# logic_analyser.net
KiCad netlist of a schematic drawn in EAGLE
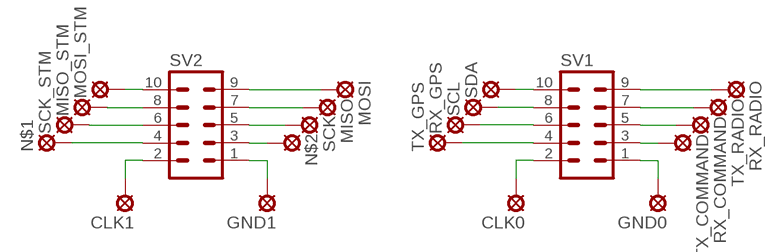
[diagram p0: schematic, sheet 1]

(export (version "E")
  (design (tool "Eeschema 10.0.6"))
  (components
    (comp (ref "CLK0")
      (value "LSP10")
      (footprint "eagle-import:LSP10")
      (libsource (lib "eagle-import") (part "LSP10"))
    )
    (comp (ref "CLK1")
      (value "LSP10")
      (footprint "eagle-import:LSP10")
      (libsource (lib "eagle-import") (part "LSP10"))
    )
    (comp (ref "GND0")
      (value "LSP10")
      (footprint "eagle-import:LSP10")
      (libsource (lib "eagle-import") (part "LSP10"))
    )
    (comp (ref "GND1")
      (value "LSP10")
      (footprint "eagle-import:LSP10")
      (libsource (lib "eagle-import") (part "LSP10"))
    )
    (comp (ref "MISO")
      (value "LSP10")
      (footprint "eagle-import:LSP10")
      (libsource (lib "eagle-import") (part "LSP10"))
    )
    (comp (ref "MISO_STM")
      (value "LSP10")
      (footprint "eagle-import:LSP10")
      (libsource (lib "eagle-import") (part "LSP10"))
    )
    (comp (ref "MOSI")
      (value "LSP10")
      (footprint "eagle-import:LSP10")
      (libsource (lib "eagle-import") (part "LSP10"))
    )
    (comp (ref "MOSI_STM")
      (value "LSP10")
      (footprint "eagle-import:LSP10")
      (libsource (lib "eagle-import") (part "LSP10"))
    )
    (comp (ref "N$1")
      (value "LSP10")
      (footprint "eagle-import:LSP10")
      (libsource (lib "eagle-import") (part "LSP10"))
    )
    (comp (ref "N$2")
      (value "LSP10")
      (footprint "eagle-import:LSP10")
      (libsource (lib "eagle-import") (part "LSP10"))
    )
    (comp (ref "RX_COMMAND")
      (value "LSP10")
      (footprint "eagle-import:LSP10")
      (libsource (lib "eagle-import") (part "LSP10"))
    )
    (comp (ref "RX_GPS")
      (value "LSP10")
      (footprint "eagle-import:LSP10")
      (libsource (lib "eagle-import") (part "LSP10"))
    )
    (comp (ref "RX_RADIO")
      (value "LSP10")
      (footprint "eagle-import:LSP10")
      (libsource (lib "eagle-import") (part "LSP10"))
    )
    (comp (ref "SCK")
      (value "LSP10")
      (footprint "eagle-import:LSP10")
      (libsource (lib "eagle-import") (part "LSP10"))
    )
    (comp (ref "SCK_STM")
      (value "LSP10")
      (footprint "eagle-import:LSP10")
      (libsource (lib "eagle-import") (part "LSP10"))
    )
    (comp (ref "SCL")
      (value "LSP10")
      (footprint "eagle-import:LSP10")
      (libsource (lib "eagle-import") (part "LSP10"))
    )
    (comp (ref "SDA")
      (value "LSP10")
      (footprint "eagle-import:LSP10")
      (libsource (lib "eagle-import") (part "LSP10"))
    )
    (comp (ref "SV1")
      (value "MA05-2")
      (footprint "eagle-import:MA05-2")
      (libsource (lib "eagle-import") (part "MA05-2"))
    )
    (comp (ref "SV2")
      (value "MA05-2")
      (footprint "eagle-import:MA05-2")
      (libsource (lib "eagle-import") (part "MA05-2"))
    )
    (comp (ref "TX_COMMAND")
      (value "LSP10")
      (footprint "eagle-import:LSP10")
      (libsource (lib "eagle-import") (part "LSP10"))
    )
    (comp (ref "TX_GPS")
      (value "LSP10")
      (footprint "eagle-import:LSP10")
      (libsource (lib "eagle-import") (part "LSP10"))
    )
    (comp (ref "TX_RADIO")
      (value "LSP10")
      (footprint "eagle-import:LSP10")
      (libsource (lib "eagle-import") (part "LSP10"))
    )
  )
  (nets
    (net (code "1") (name "Net-(CLK0-PadMP)") (class "Default")
      (node (ref "CLK0") (pin "MP") (pinfunction "MP_MP") (pintype "passive"))
      (node (ref "SV1") (pin "2") (pinfunction "2_2") (pintype "passive"))
    )
    (net (code "2") (name "Net-(CLK1-PadMP)") (class "Default")
      (node (ref "CLK1") (pin "MP") (pinfunction "MP_MP") (pintype "passive"))
      (node (ref "SV2") (pin "2") (pinfunction "2_2") (pintype "passive"))
    )
    (net (code "3") (name "Net-(GND0-PadMP)") (class "Default")
      (node (ref "GND0") (pin "MP") (pinfunction "MP_MP") (pintype "passive"))
      (node (ref "SV1") (pin "1") (pinfunction "1_1") (pintype "passive"))
    )
    (net (code "4") (name "Net-(GND1-PadMP)") (class "Default")
      (node (ref "GND1") (pin "MP") (pinfunction "MP_MP") (pintype "passive"))
      (node (ref "SV2") (pin "1") (pinfunction "1_1") (pintype "passive"))
    )
    (net (code "5") (name "Net-(MISO-PadMP)") (class "Default")
      (node (ref "MISO") (pin "MP") (pinfunction "MP_MP") (pintype "passive"))
      (node (ref "SV2") (pin "7") (pinfunction "7_7") (pintype "passive"))
    )
    (net (code "6") (name "Net-(MISO_STM-PadMP)") (class "Default")
      (node (ref "MISO_STM") (pin "MP") (pinfunction "MP_MP") (pintype "passive"))
      (node (ref "SV2") (pin "8") (pinfunction "8_8") (pintype "passive"))
    )
    (net (code "7") (name "Net-(MOSI-PadMP)") (class "Default")
      (node (ref "MOSI") (pin "MP") (pinfunction "MP_MP") (pintype "passive"))
      (node (ref "SV2") (pin "9") (pinfunction "9_9") (pintype "passive"))
    )
    (net (code "8") (name "Net-(MOSI_STM-PadMP)") (class "Default")
      (node (ref "MOSI_STM") (pin "MP") (pinfunction "MP_MP") (pintype "passive"))
      (node (ref "SV2") (pin "10") (pinfunction "10_10") (pintype "passive"))
    )
    (net (code "9") (name "Net-(N$1-PadMP)") (class "Default")
      (node (ref "N$1") (pin "MP") (pinfunction "MP_MP") (pintype "passive"))
      (node (ref "SV2") (pin "4") (pinfunction "4_4") (pintype "passive"))
    )
    (net (code "10") (name "Net-(N$2-PadMP)") (class "Default")
      (node (ref "N$2") (pin "MP") (pinfunction "MP_MP") (pintype "passive"))
      (node (ref "SV2") (pin "3") (pinfunction "3_3") (pintype "passive"))
    )
    (net (code "11") (name "Net-(RX_COMMAND-PadMP)") (class "Default")
      (node (ref "RX_COMMAND") (pin "MP") (pinfunction "MP_MP") (pintype "passive"))
      (node (ref "SV1") (pin "5") (pinfunction "5_5") (pintype "passive"))
    )
    (net (code "12") (name "Net-(RX_GPS-PadMP)") (class "Default")
      (node (ref "RX_GPS") (pin "MP") (pinfunction "MP_MP") (pintype "passive"))
      (node (ref "SV1") (pin "6") (pinfunction "6_6") (pintype "passive"))
    )
    (net (code "13") (name "Net-(RX_RADIO-PadMP)") (class "Default")
      (node (ref "RX_RADIO") (pin "MP") (pinfunction "MP_MP") (pintype "passive"))
      (node (ref "SV1") (pin "9") (pinfunction "9_9") (pintype "passive"))
    )
    (net (code "14") (name "Net-(SCK-PadMP)") (class "Default")
      (node (ref "SCK") (pin "MP") (pinfunction "MP_MP") (pintype "passive"))
      (node (ref "SV2") (pin "5") (pinfunction "5_5") (pintype "passive"))
    )
    (net (code "15") (name "Net-(SCK_STM-PadMP)") (class "Default")
      (node (ref "SCK_STM") (pin "MP") (pinfunction "MP_MP") (pintype "passive"))
      (node (ref "SV2") (pin "6") (pinfunction "6_6") (pintype "passive"))
    )
    (net (code "16") (name "Net-(SCL-PadMP)") (class "Default")
      (node (ref "SCL") (pin "MP") (pinfunction "MP_MP") (pintype "passive"))
      (node (ref "SV1") (pin "8") (pinfunction "8_8") (pintype "passive"))
    )
    (net (code "17") (name "Net-(SDA-PadMP)") (class "Default")
      (node (ref "SDA") (pin "MP") (pinfunction "MP_MP") (pintype "passive"))
      (node (ref "SV1") (pin "10") (pinfunction "10_10") (pintype "passive"))
    )
    (net (code "18") (name "Net-(SV1-Pad3)") (class "Default")
      (node (ref "SV1") (pin "3") (pinfunction "3_3") (pintype "passive"))
      (node (ref "TX_COMMAND") (pin "MP") (pinfunction "MP_MP") (pintype "passive"))
    )
    (net (code "19") (name "Net-(SV1-Pad4)") (class "Default")
      (node (ref "SV1") (pin "4") (pinfunction "4_4") (pintype "passive"))
      (node (ref "TX_GPS") (pin "MP") (pinfunction "MP_MP") (pintype "passive"))
    )
    (net (code "20") (name "Net-(SV1-Pad7)") (class "Default")
      (node (ref "SV1") (pin "7") (pinfunction "7_7") (pintype "passive"))
      (node (ref "TX_RADIO") (pin "MP") (pinfunction "MP_MP") (pintype "passive"))
    )
  )
)
